# Flasherrev2.net
KiCad netlist of a schematic drawn in EAGLE
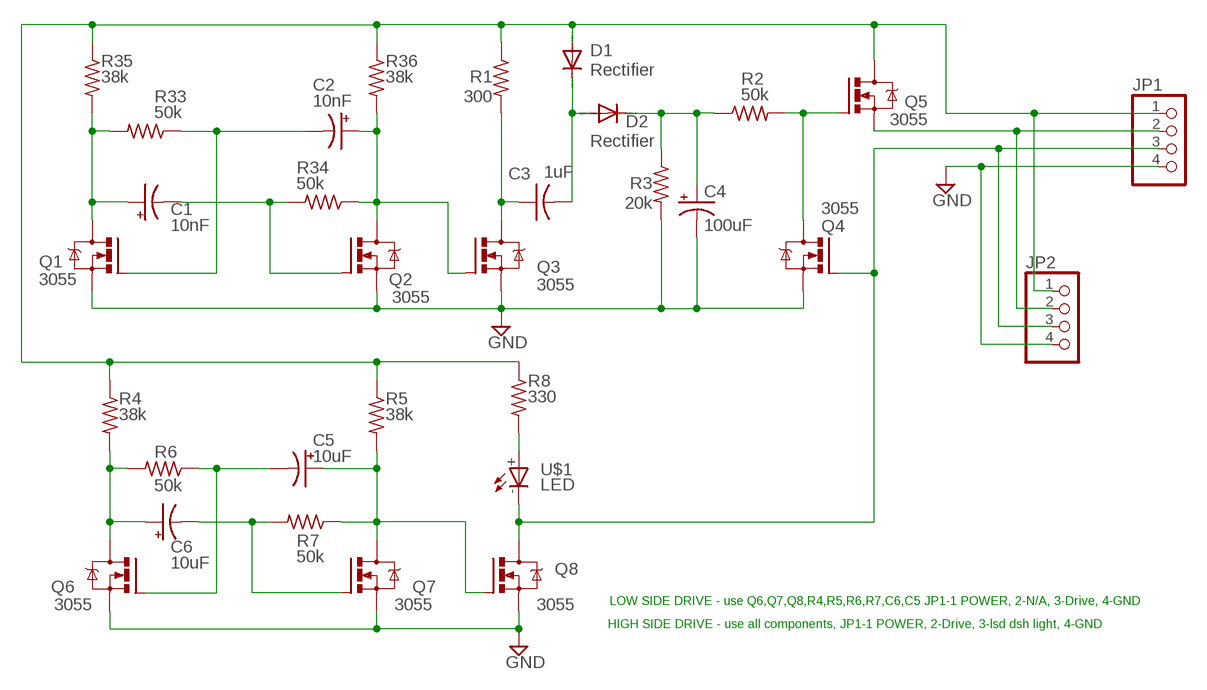
[diagram p0: schematic, sheet 1]

(export (version "E")
  (design (tool "Eeschema 10.0.6"))
  (components
    (comp (ref "C1")
      (value "10nF")
      (footprint "eagle-import:CT3528")
      (libsource (lib "eagle-import") (part "CPOL-USCT3528"))
    )
    (comp (ref "C2")
      (value "10nF")
      (footprint "eagle-import:CT3528")
      (libsource (lib "eagle-import") (part "CPOL-USCT3528"))
    )
    (comp (ref "C3")
      (value "1uF")
      (footprint "eagle-import:C1206")
      (libsource (lib "eagle-import") (part "CAPACITOR-NO-POLARITYC1206"))
    )
    (comp (ref "C4")
      (value "100uF")
      (footprint "eagle-import:PANASONIC_F")
      (libsource (lib "eagle-import") (part "CPOL-USF"))
    )
    (comp (ref "C5")
      (value "10uF")
      (footprint "eagle-import:CT3528")
      (libsource (lib "eagle-import") (part "CPOL-USCT3528"))
    )
    (comp (ref "C6")
      (value "10uF")
      (footprint "eagle-import:CT3528")
      (libsource (lib "eagle-import") (part "CPOL-USCT3528"))
    )
    (comp (ref "D1")
      (value "Rectifier")
      (footprint "eagle-import:DO-214AC")
      (libsource (lib "eagle-import") (part "DIODE-DO-214AC"))
    )
    (comp (ref "D2")
      (value "Rectifier")
      (footprint "eagle-import:DO-214AC")
      (libsource (lib "eagle-import") (part "DIODE-DO-214AC"))
    )
    (comp (ref "JP1")
      (value "PINHD-1X4")
      (footprint "eagle-import:1X04")
      (libsource (lib "eagle-import") (part "PINHD-1X4"))
    )
    (comp (ref "JP2")
      (value "PINHD-1X4")
      (footprint "eagle-import:1X04")
      (libsource (lib "eagle-import") (part "PINHD-1X4"))
    )
    (comp (ref "Q1")
      (value "3055")
      (footprint "eagle-import:SOT223R_INFINEON")
      (libsource (lib "eagle-import") (part "MTP3055VSOIC"))
    )
    (comp (ref "Q2")
      (value "3055")
      (footprint "eagle-import:SOT223R_INFINEON")
      (libsource (lib "eagle-import") (part "MTP3055VSOIC"))
    )
    (comp (ref "Q3")
      (value "3055")
      (footprint "eagle-import:SOT223R_INFINEON")
      (libsource (lib "eagle-import") (part "MTP3055VSOIC"))
    )
    (comp (ref "Q4")
      (value "3055")
      (footprint "eagle-import:SOT223R_INFINEON")
      (libsource (lib "eagle-import") (part "MTP3055VSOIC"))
    )
    (comp (ref "Q5")
      (value "3055")
      (footprint "eagle-import:TO220BV")
      (libsource (lib "eagle-import") (part "MTP3055V"))
    )
    (comp (ref "Q6")
      (value "3055")
      (footprint "eagle-import:SOT223R_INFINEON")
      (libsource (lib "eagle-import") (part "MTP3055VSOIC"))
    )
    (comp (ref "Q7")
      (value "3055")
      (footprint "eagle-import:SOT223R_INFINEON")
      (libsource (lib "eagle-import") (part "MTP3055VSOIC"))
    )
    (comp (ref "Q8")
      (value "3055")
      (footprint "eagle-import:TO220BV")
      (libsource (lib "eagle-import") (part "MTP3055V"))
    )
    (comp (ref "R1")
      (value "300")
      (footprint "eagle-import:R1206")
      (libsource (lib "eagle-import") (part "RESISITORR1206"))
    )
    (comp (ref "R2")
      (value "50k")
      (footprint "eagle-import:R1206")
      (libsource (lib "eagle-import") (part "RESISITORR1206"))
    )
    (comp (ref "R3")
      (value "20k")
      (footprint "eagle-import:R1206")
      (libsource (lib "eagle-import") (part "RESISITORR1206"))
    )
    (comp (ref "R4")
      (value "38k")
      (footprint "eagle-import:R1206")
      (libsource (lib "eagle-import") (part "RESISITORR1206"))
    )
    (comp (ref "R5")
      (value "38k")
      (footprint "eagle-import:R1206")
      (libsource (lib "eagle-import") (part "RESISITORR1206"))
    )
    (comp (ref "R6")
      (value "50k")
      (footprint "eagle-import:R1206")
      (libsource (lib "eagle-import") (part "RESISITORR1206"))
    )
    (comp (ref "R7")
      (value "50k")
      (footprint "eagle-import:R1206")
      (libsource (lib "eagle-import") (part "RESISITORR1206"))
    )
    (comp (ref "R8")
      (value "330")
      (footprint "eagle-import:R1206")
      (libsource (lib "eagle-import") (part "RESISITORR1206"))
    )
    (comp (ref "R33")
      (value "50k")
      (footprint "eagle-import:R1206")
      (libsource (lib "eagle-import") (part "RESISITORR1206"))
    )
    (comp (ref "R34")
      (value "50k")
      (footprint "eagle-import:R1206")
      (libsource (lib "eagle-import") (part "RESISITORR1206"))
    )
    (comp (ref "R35")
      (value "38k")
      (footprint "eagle-import:R1206")
      (libsource (lib "eagle-import") (part "RESISITORR1206"))
    )
    (comp (ref "R36")
      (value "38k")
      (footprint "eagle-import:R1206")
      (libsource (lib "eagle-import") (part "RESISITORR1206"))
    )
    (comp (ref "U$1")
      (value "LED")
      (footprint "eagle-import:1206")
      (libsource (lib "eagle-import") (part "LED"))
    )
  )
  (nets
    (net (code "1") (name "GND") (class "Default")
      (node (ref "C4") (pin "-") (pinfunction "-_-") (pintype "passive"))
      (node (ref "JP1") (pin "4") (pinfunction "4_4") (pintype "passive"))
      (node (ref "JP2") (pin "4") (pinfunction "4_4") (pintype "passive"))
      (node (ref "Q1") (pin "3") (pinfunction "S_3") (pintype "passive"))
      (node (ref "Q2") (pin "3") (pinfunction "S_3") (pintype "passive"))
      (node (ref "Q3") (pin "3") (pinfunction "S_3") (pintype "passive"))
      (node (ref "Q4") (pin "3") (pinfunction "S_3") (pintype "passive"))
      (node (ref "Q6") (pin "3") (pinfunction "S_3") (pintype "passive"))
      (node (ref "Q7") (pin "3") (pinfunction "S_3") (pintype "passive"))
      (node (ref "Q8") (pin "S") (pinfunction "S_S") (pintype "passive"))
      (node (ref "R3") (pin "2") (pinfunction "2_2") (pintype "passive"))
    )
    (net (code "2") (name "Net-(C3-Pad2)") (class "Default")
      (node (ref "C3") (pin "2") (pinfunction "2_2") (pintype "passive"))
      (node (ref "D1") (pin "C") (pinfunction "C_C") (pintype "passive"))
      (node (ref "D2") (pin "A") (pinfunction "A_A") (pintype "passive"))
    )
    (net (code "3") (name "Net-(C4-Pad+)") (class "Default")
      (node (ref "C4") (pin "+") (pinfunction "+_+") (pintype "passive"))
      (node (ref "D2") (pin "C") (pinfunction "C_C") (pintype "passive"))
      (node (ref "R2") (pin "1") (pinfunction "1_1") (pintype "passive"))
      (node (ref "R3") (pin "1") (pinfunction "1_1") (pintype "passive"))
    )
    (net (code "4") (name "Net-(D1-PadA)") (class "Default")
      (node (ref "D1") (pin "A") (pinfunction "A_A") (pintype "passive"))
      (node (ref "JP1") (pin "1") (pinfunction "1_1") (pintype "passive"))
      (node (ref "JP2") (pin "1") (pinfunction "1_1") (pintype "passive"))
      (node (ref "Q5") (pin "D") (pinfunction "D_D") (pintype "passive"))
      (node (ref "R1") (pin "1") (pinfunction "1_1") (pintype "passive"))
      (node (ref "R35") (pin "1") (pinfunction "1_1") (pintype "passive"))
      (node (ref "R36") (pin "1") (pinfunction "1_1") (pintype "passive"))
      (node (ref "R4") (pin "1") (pinfunction "1_1") (pintype "passive"))
      (node (ref "R5") (pin "1") (pinfunction "1_1") (pintype "passive"))
      (node (ref "R8") (pin "1") (pinfunction "1_1") (pintype "passive"))
    )
    (net (code "5") (name "Net-(JP1-Pad2)") (class "Default")
      (node (ref "JP1") (pin "2") (pinfunction "2_2") (pintype "passive"))
      (node (ref "JP2") (pin "2") (pinfunction "2_2") (pintype "passive"))
      (node (ref "Q5") (pin "S") (pinfunction "S_S") (pintype "passive"))
    )
    (net (code "6") (name "Net-(Q1-D)") (class "Default")
      (node (ref "C1") (pin "+") (pinfunction "+_+") (pintype "passive"))
      (node (ref "Q1") (pin "2") (pinfunction "D_2") (pintype "passive"))
      (node (ref "R33") (pin "2") (pinfunction "2_2") (pintype "passive"))
      (node (ref "R35") (pin "2") (pinfunction "2_2") (pintype "passive"))
    )
    (net (code "7") (name "Net-(Q1-G)") (class "Default")
      (node (ref "C2") (pin "-") (pinfunction "-_-") (pintype "passive"))
      (node (ref "Q1") (pin "1") (pinfunction "G_1") (pintype "passive"))
      (node (ref "R33") (pin "1") (pinfunction "1_1") (pintype "passive"))
    )
    (net (code "8") (name "Net-(Q2-D)") (class "Default")
      (node (ref "C2") (pin "+") (pinfunction "+_+") (pintype "passive"))
      (node (ref "Q2") (pin "2") (pinfunction "D_2") (pintype "passive"))
      (node (ref "Q3") (pin "1") (pinfunction "G_1") (pintype "passive"))
      (node (ref "R34") (pin "1") (pinfunction "1_1") (pintype "passive"))
      (node (ref "R36") (pin "2") (pinfunction "2_2") (pintype "passive"))
    )
    (net (code "9") (name "Net-(Q2-G)") (class "Default")
      (node (ref "C1") (pin "-") (pinfunction "-_-") (pintype "passive"))
      (node (ref "Q2") (pin "1") (pinfunction "G_1") (pintype "passive"))
      (node (ref "R34") (pin "2") (pinfunction "2_2") (pintype "passive"))
    )
    (net (code "10") (name "Net-(Q3-D)") (class "Default")
      (node (ref "C3") (pin "1") (pinfunction "1_1") (pintype "passive"))
      (node (ref "Q3") (pin "2") (pinfunction "D_2") (pintype "passive"))
      (node (ref "R1") (pin "2") (pinfunction "2_2") (pintype "passive"))
    )
    (net (code "11") (name "Net-(Q4-D)") (class "Default")
      (node (ref "Q4") (pin "2") (pinfunction "D_2") (pintype "passive"))
      (node (ref "Q5") (pin "G") (pinfunction "G_G") (pintype "passive"))
      (node (ref "R2") (pin "2") (pinfunction "2_2") (pintype "passive"))
    )
    (net (code "12") (name "Net-(Q4-G)") (class "Default")
      (node (ref "JP1") (pin "3") (pinfunction "3_3") (pintype "passive"))
      (node (ref "JP2") (pin "3") (pinfunction "3_3") (pintype "passive"))
      (node (ref "Q4") (pin "1") (pinfunction "G_1") (pintype "passive"))
      (node (ref "Q8") (pin "D") (pinfunction "D_D") (pintype "passive"))
      (node (ref "U$1") (pin "-") (pinfunction "-_-") (pintype "passive"))
    )
    (net (code "13") (name "Net-(Q6-D)") (class "Default")
      (node (ref "C6") (pin "+") (pinfunction "+_+") (pintype "passive"))
      (node (ref "Q6") (pin "2") (pinfunction "D_2") (pintype "passive"))
      (node (ref "R4") (pin "2") (pinfunction "2_2") (pintype "passive"))
      (node (ref "R6") (pin "2") (pinfunction "2_2") (pintype "passive"))
    )
    (net (code "14") (name "Net-(Q6-G)") (class "Default")
      (node (ref "C5") (pin "-") (pinfunction "-_-") (pintype "passive"))
      (node (ref "Q6") (pin "1") (pinfunction "G_1") (pintype "passive"))
      (node (ref "R6") (pin "1") (pinfunction "1_1") (pintype "passive"))
    )
    (net (code "15") (name "Net-(Q7-D)") (class "Default")
      (node (ref "C5") (pin "+") (pinfunction "+_+") (pintype "passive"))
      (node (ref "Q7") (pin "2") (pinfunction "D_2") (pintype "passive"))
      (node (ref "Q8") (pin "G") (pinfunction "G_G") (pintype "passive"))
      (node (ref "R5") (pin "2") (pinfunction "2_2") (pintype "passive"))
      (node (ref "R7") (pin "1") (pinfunction "1_1") (pintype "passive"))
    )
    (net (code "16") (name "Net-(Q7-G)") (class "Default")
      (node (ref "C6") (pin "-") (pinfunction "-_-") (pintype "passive"))
      (node (ref "Q7") (pin "1") (pinfunction "G_1") (pintype "passive"))
      (node (ref "R7") (pin "2") (pinfunction "2_2") (pintype "passive"))
    )
    (net (code "17") (name "Net-(R8-Pad2)") (class "Default")
      (node (ref "R8") (pin "2") (pinfunction "2_2") (pintype "passive"))
      (node (ref "U$1") (pin "+") (pinfunction "+_+") (pintype "passive"))
    )
  )
)
